# Top.net
KiCad netlist of a schematic drawn in Altium Designer
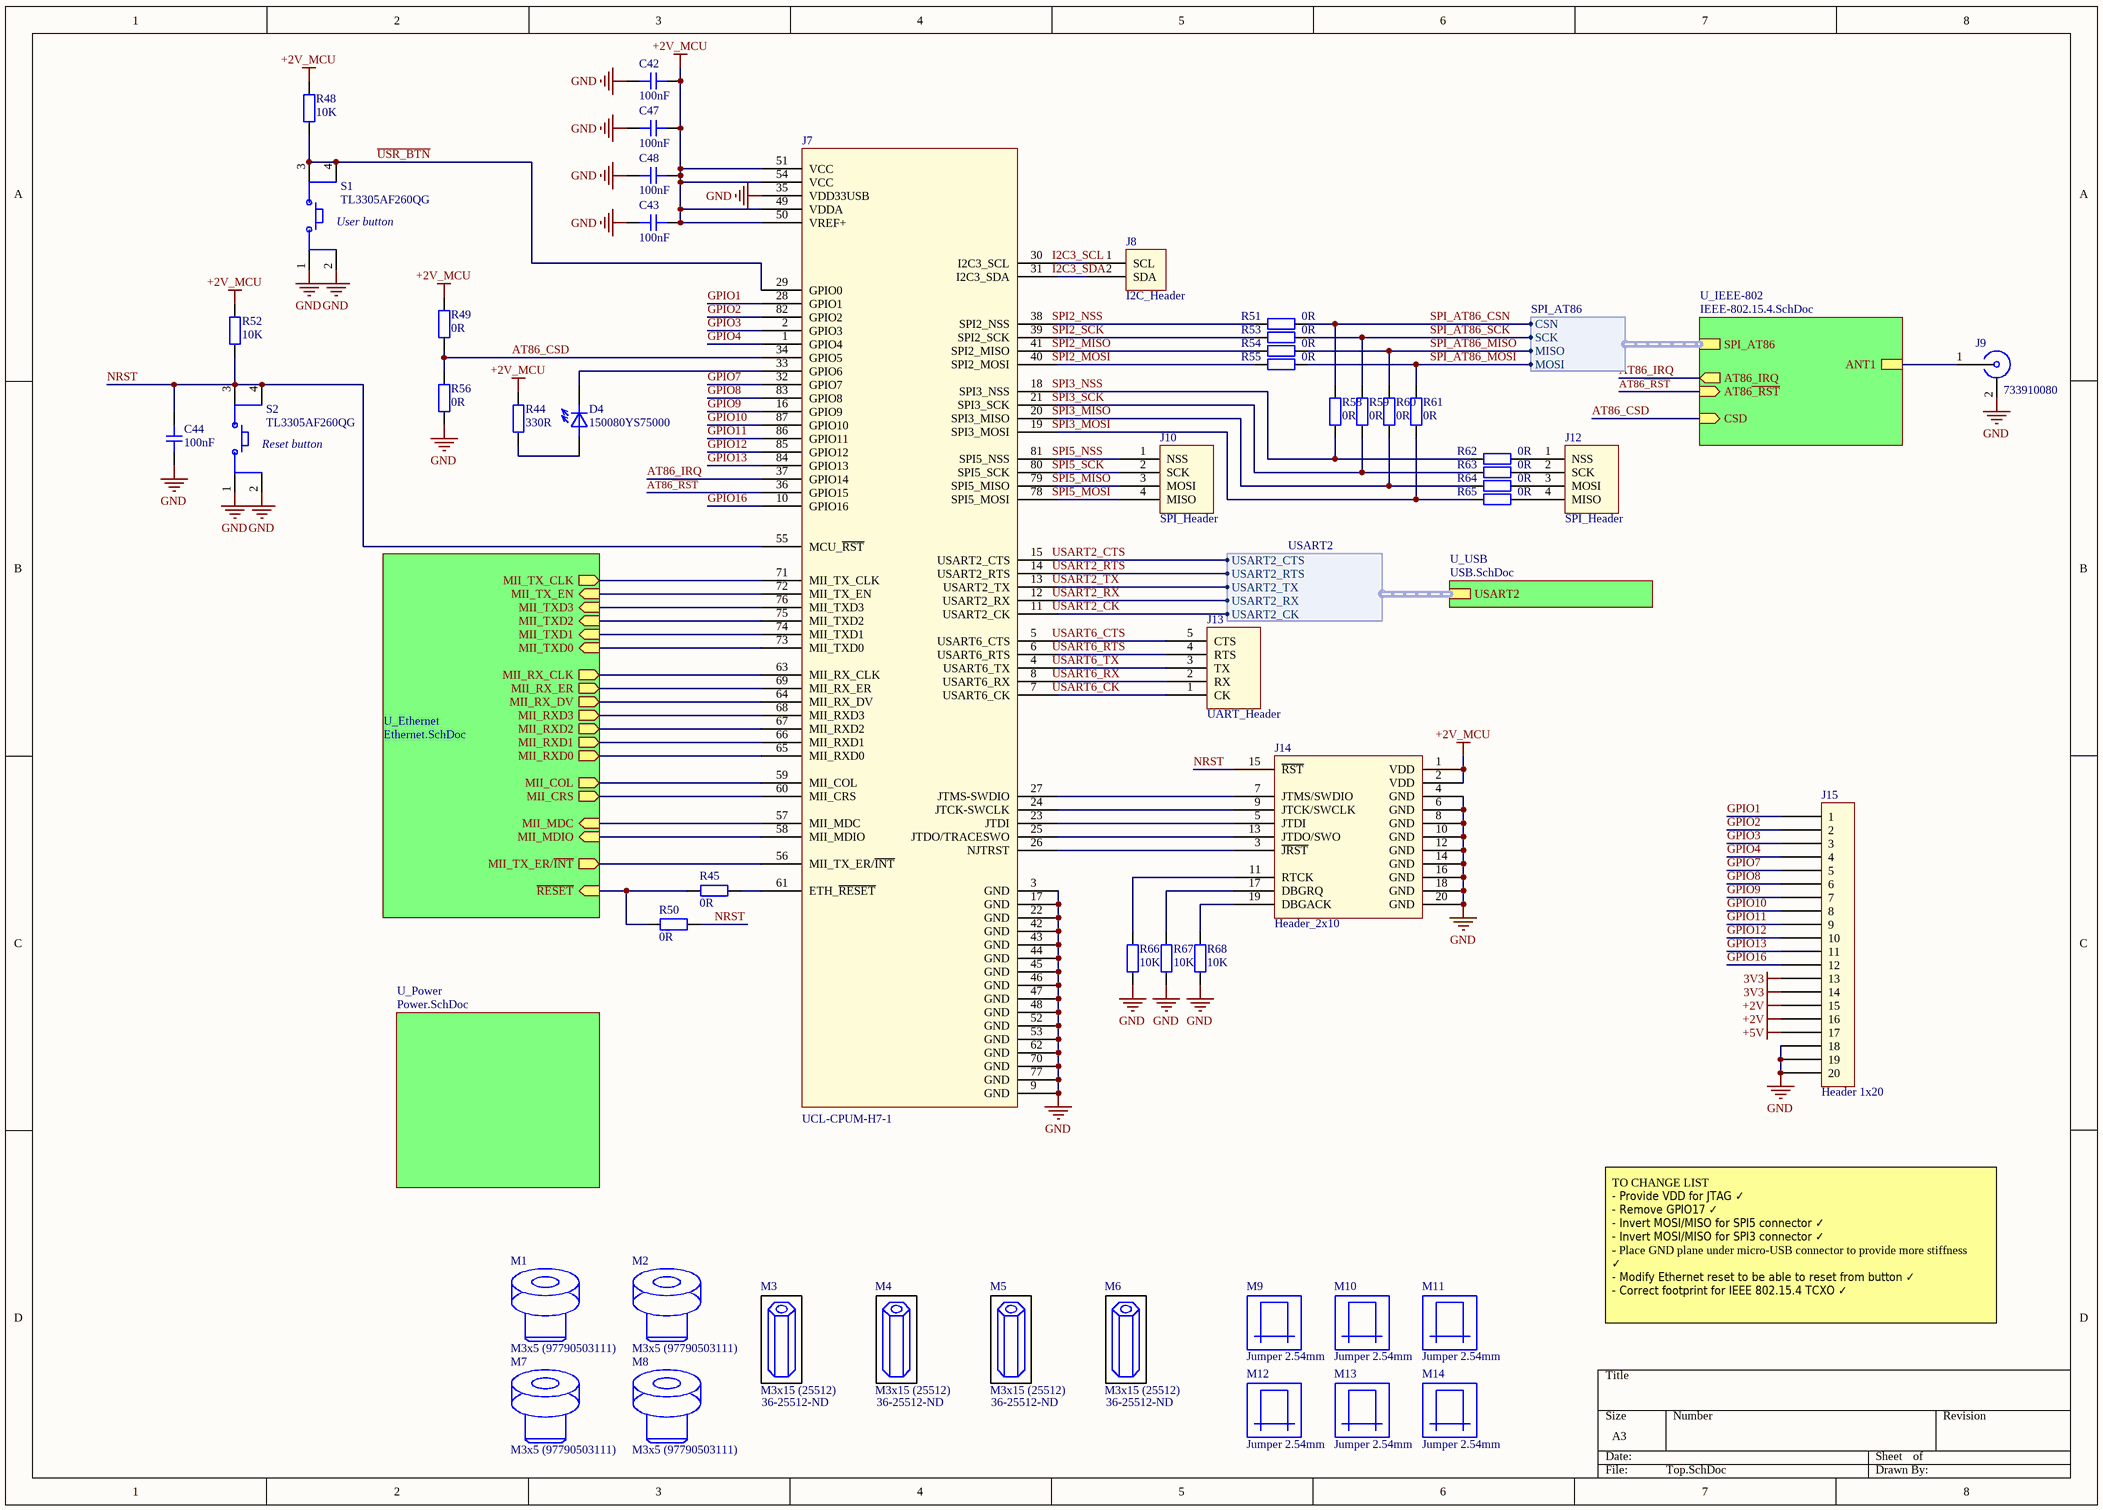
[diagram p0: Top.SchDoc]

(export (version "E")
  (design (tool "Eeschema 10.0.6"))
  (components
    (comp (ref "C42")
      (value "100nF")
      (footprint "Capacitor-0603")
      (fields (field (name "Comment") "C-100nF-0603"))
      (libsource (lib "Components") (part "C-100nF-0603"))
    )
    (comp (ref "C43")
      (value "100nF")
      (footprint "Capacitor-0603")
      (fields (field (name "Comment") "C-100nF-0603"))
      (libsource (lib "Components") (part "C-100nF-0603"))
    )
    (comp (ref "C44")
      (value "100nF")
      (footprint "Capacitor-0603")
      (fields (field (name "Comment") "C-100nF-0603"))
      (libsource (lib "Components") (part "C-100nF-0603"))
    )
    (comp (ref "C47")
      (value "100nF")
      (footprint "Capacitor-0603")
      (fields (field (name "Comment") "C-100nF-0603"))
      (libsource (lib "Components") (part "C-100nF-0603"))
    )
    (comp (ref "C48")
      (value "100nF")
      (footprint "Capacitor-0603")
      (fields (field (name "Comment") "C-100nF-0603"))
      (libsource (lib "Components") (part "C-100nF-0603"))
    )
    (comp (ref "D4")
      (value "150080YS75000")
      (footprint "150080YS75000")
      (libsource (lib "Components") (part "150080YS75000"))
    )
    (comp (ref "J7")
      (value "UCL-CPUM-H7-1")
      (footprint "UCL-CPUM-H7-1")
      (libsource (lib "Components") (part "UCL-CPUM-H7-1"))
    )
    (comp (ref "J8")
      (value "I2C_Header")
      (footprint "I2C_header")
      (libsource (lib "Components") (part "I2C_Header"))
    )
    (comp (ref "J9")
      (value "733910080")
      (footprint "SMA_733910080")
      (libsource (lib "Components") (part "SMA_733910080"))
    )
    (comp (ref "J10")
      (value "SPI_Header")
      (footprint "SPI_Header")
      (libsource (lib "Components") (part "SPI_Header"))
    )
    (comp (ref "J12")
      (value "SPI_Header")
      (footprint "SPI_Header")
      (libsource (lib "Components") (part "SPI_Header"))
    )
    (comp (ref "J13")
      (value "UART_Header")
      (footprint "UART_Header")
      (libsource (lib "Components") (part "UART_Header"))
    )
    (comp (ref "J14")
      (value "Header_2x10")
      (footprint "JTAG_Header")
      (libsource (lib "Components") (part "JTAG_Header"))
    )
    (comp (ref "J15")
      (value "Header 1x20")
      (footprint "GPIO_Header")
      (libsource (lib "Components") (part "GPIO_Header"))
    )
    (comp (ref "M1")
      (value "M3x5 (97790503111)")
      (footprint "Screw_M3")
      (libsource (lib "Components") (part "Screw_M3x5"))
    )
    (comp (ref "M2")
      (value "M3x5 (97790503111)")
      (footprint "Screw_M3")
      (libsource (lib "Components") (part "Screw_M3x5"))
    )
    (comp (ref "M3")
      (value "M3x15 (25512)")
      (fields (field (name "SUPPLIER PART NUMBER 1") "36-25512-ND"))
      (libsource (lib "Components") (part "Standoff_hex_M3_15mm_25512"))
    )
    (comp (ref "M4")
      (value "M3x15 (25512)")
      (fields (field (name "SUPPLIER PART NUMBER 1") "36-25512-ND"))
      (libsource (lib "Components") (part "Standoff_hex_M3_15mm_25512"))
    )
    (comp (ref "M5")
      (value "M3x15 (25512)")
      (fields (field (name "SUPPLIER PART NUMBER 1") "36-25512-ND"))
      (libsource (lib "Components") (part "Standoff_hex_M3_15mm_25512"))
    )
    (comp (ref "M6")
      (value "M3x15 (25512)")
      (fields (field (name "SUPPLIER PART NUMBER 1") "36-25512-ND"))
      (libsource (lib "Components") (part "Standoff_hex_M3_15mm_25512"))
    )
    (comp (ref "M7")
      (value "M3x5 (97790503111)")
      (footprint "Screw_M3")
      (libsource (lib "Components") (part "Screw_M3x5"))
    )
    (comp (ref "M8")
      (value "M3x5 (97790503111)")
      (footprint "Screw_M3")
      (libsource (lib "Components") (part "Screw_M3x5"))
    )
    (comp (ref "M9") (value "Jumper 2.54mm") (libsource (lib "Components") (part "QPC02SXGN-RC")))
    (comp (ref "M10") (value "Jumper 2.54mm") (libsource (lib "Components") (part "QPC02SXGN-RC")))
    (comp (ref "M11") (value "Jumper 2.54mm") (libsource (lib "Components") (part "QPC02SXGN-RC")))
    (comp (ref "M12") (value "Jumper 2.54mm") (libsource (lib "Components") (part "QPC02SXGN-RC")))
    (comp (ref "M13") (value "Jumper 2.54mm") (libsource (lib "Components") (part "QPC02SXGN-RC")))
    (comp (ref "M14") (value "Jumper 2.54mm") (libsource (lib "Components") (part "QPC02SXGN-RC")))
    (comp (ref "R44")
      (value "330R")
      (footprint "Resistor-0603")
      (fields (field (name "Comment") "R-330R-0603"))
      (libsource (lib "Components") (part "R-330R-0603"))
    )
    (comp (ref "R45")
      (value "0R")
      (footprint "Resistor-0603")
      (fields (field (name "Comment") "R-0R-0603"))
      (libsource (lib "Components") (part "R-0R-0603"))
    )
    (comp (ref "R48")
      (value "10K")
      (footprint "Resistor-0603")
      (fields (field (name "Comment") "R-10K-0603"))
      (libsource (lib "Components") (part "R-10K-0603"))
    )
    (comp (ref "R49")
      (value "0R")
      (footprint "Resistor-0603")
      (fields (field (name "Comment") "R-0R-0603"))
      (libsource (lib "Components") (part "R-0R-0603"))
    )
    (comp (ref "R50")
      (value "0R")
      (footprint "Resistor-0603")
      (fields (field (name "Comment") "R-0R-0603"))
      (libsource (lib "Components") (part "R-0R-0603"))
    )
    (comp (ref "R51")
      (value "0R")
      (footprint "Resistor-0603")
      (fields (field (name "Comment") "R-0R-0603"))
      (libsource (lib "Components") (part "R-0R-0603"))
    )
    (comp (ref "R52")
      (value "10K")
      (footprint "Resistor-0603")
      (fields (field (name "Comment") "R-10K-0603"))
      (libsource (lib "Components") (part "R-10K-0603"))
    )
    (comp (ref "R53")
      (value "0R")
      (footprint "Resistor-0603")
      (fields (field (name "Comment") "R-0R-0603"))
      (libsource (lib "Components") (part "R-0R-0603"))
    )
    (comp (ref "R54")
      (value "0R")
      (footprint "Resistor-0603")
      (fields (field (name "Comment") "R-0R-0603"))
      (libsource (lib "Components") (part "R-0R-0603"))
    )
    (comp (ref "R55")
      (value "0R")
      (footprint "Resistor-0603")
      (fields (field (name "Comment") "R-0R-0603"))
      (libsource (lib "Components") (part "R-0R-0603"))
    )
    (comp (ref "R56")
      (value "0R")
      (footprint "Resistor-0603")
      (fields (field (name "Comment") "R-0R-0603"))
      (libsource (lib "Components") (part "R-0R-0603"))
    )
    (comp (ref "R58")
      (value "0R")
      (footprint "Resistor-0603")
      (fields (field (name "Comment") "R-0R-0603"))
      (libsource (lib "Components") (part "R-0R-0603"))
    )
    (comp (ref "R59")
      (value "0R")
      (footprint "Resistor-0603")
      (fields (field (name "Comment") "R-0R-0603"))
      (libsource (lib "Components") (part "R-0R-0603"))
    )
    (comp (ref "R60")
      (value "0R")
      (footprint "Resistor-0603")
      (fields (field (name "Comment") "R-0R-0603"))
      (libsource (lib "Components") (part "R-0R-0603"))
    )
    (comp (ref "R61")
      (value "0R")
      (footprint "Resistor-0603")
      (fields (field (name "Comment") "R-0R-0603"))
      (libsource (lib "Components") (part "R-0R-0603"))
    )
    (comp (ref "R62")
      (value "0R")
      (footprint "Resistor-0603")
      (fields (field (name "Comment") "R-0R-0603"))
      (libsource (lib "Components") (part "R-0R-0603"))
    )
    (comp (ref "R63")
      (value "0R")
      (footprint "Resistor-0603")
      (fields (field (name "Comment") "R-0R-0603"))
      (libsource (lib "Components") (part "R-0R-0603"))
    )
    (comp (ref "R64")
      (value "0R")
      (footprint "Resistor-0603")
      (fields (field (name "Comment") "R-0R-0603"))
      (libsource (lib "Components") (part "R-0R-0603"))
    )
    (comp (ref "R65")
      (value "0R")
      (footprint "Resistor-0603")
      (fields (field (name "Comment") "R-0R-0603"))
      (libsource (lib "Components") (part "R-0R-0603"))
    )
    (comp (ref "R66")
      (value "10K")
      (footprint "Resistor-0603")
      (fields (field (name "Comment") "R-10K-0603"))
      (libsource (lib "Components") (part "R-10K-0603"))
    )
    (comp (ref "R67")
      (value "10K")
      (footprint "Resistor-0603")
      (fields (field (name "Comment") "R-10K-0603"))
      (libsource (lib "Components") (part "R-10K-0603"))
    )
    (comp (ref "R68")
      (value "10K")
      (footprint "Resistor-0603")
      (fields (field (name "Comment") "R-10K-0603"))
      (libsource (lib "Components") (part "R-10K-0603"))
    )
    (comp (ref "S1")
      (value "TL3305AF260QG")
      (footprint "TL3305AF260QG")
      (libsource (lib "Components") (part "TL3305AF260QG"))
    )
    (comp (ref "S2")
      (value "TL3305AF260QG")
      (footprint "TL3305AF260QG")
      (libsource (lib "Components") (part "TL3305AF260QG"))
    )
  )
  (nets
    (net (code "3") (name "+2V") (class "Default")
      (node (ref "J15") (pin "15") (pinfunction "15_15") (pintype "passive"))
      (node (ref "J15") (pin "16") (pinfunction "16_16") (pintype "passive"))
    )
    (net (code "4") (name "+2V_MCU") (class "Default")
      (node (ref "C42") (pin "2") (pinfunction "2_2") (pintype "passive"))
      (node (ref "C43") (pin "2") (pinfunction "2_2") (pintype "passive"))
      (node (ref "C47") (pin "2") (pinfunction "2_2") (pintype "passive"))
      (node (ref "C48") (pin "2") (pinfunction "2_2") (pintype "passive"))
      (node (ref "J14") (pin "1") (pinfunction "VDD_1") (pintype "passive"))
      (node (ref "J14") (pin "2") (pinfunction "VDD_2") (pintype "passive"))
      (node (ref "J7") (pin "49") (pinfunction "VDDA_49") (pintype "passive"))
      (node (ref "J7") (pin "50") (pinfunction "VREF+_50") (pintype "passive"))
      (node (ref "J7") (pin "51") (pinfunction "VCC_51") (pintype "passive"))
      (node (ref "J7") (pin "54") (pinfunction "VCC_54") (pintype "passive"))
      (node (ref "R44") (pin "2") (pinfunction "2_2") (pintype "passive"))
      (node (ref "R48") (pin "2") (pinfunction "2_2") (pintype "passive"))
      (node (ref "R49") (pin "2") (pinfunction "2_2") (pintype "passive"))
      (node (ref "R52") (pin "2") (pinfunction "2_2") (pintype "passive"))
    )
    (net (code "5") (name "+5V") (class "Default")
      (node (ref "J15") (pin "17") (pinfunction "17_17") (pintype "passive"))
    )
    (net (code "6") (name "/ANT1") (class "Default")
      (node (ref "J9") (pin "1") (pinfunction "SIG_1") (pintype "passive"))
    )
    (net (code "7") (name "/AT86_CSD") (class "Default")
      (node (ref "J7") (pin "34") (pinfunction "GPIO5_34") (pintype "passive"))
      (node (ref "R49") (pin "1") (pinfunction "1_1") (pintype "passive"))
      (node (ref "R56") (pin "2") (pinfunction "2_2") (pintype "passive"))
    )
    (net (code "8") (name "/AT86_IRQ") (class "Default")
      (node (ref "J7") (pin "37") (pinfunction "GPIO14_37") (pintype "passive"))
    )
    (net (code "9") (name "/AT86~{_RST}") (class "Default")
      (node (ref "J7") (pin "36") (pinfunction "GPIO15_36") (pintype "passive"))
    )
    (net (code "10") (name "/GPIO1") (class "Default")
      (node (ref "J15") (pin "1") (pinfunction "1_1") (pintype "passive"))
      (node (ref "J7") (pin "28") (pinfunction "GPIO1_28") (pintype "passive"))
    )
    (net (code "11") (name "/GPIO2") (class "Default")
      (node (ref "J15") (pin "2") (pinfunction "2_2") (pintype "passive"))
      (node (ref "J7") (pin "82") (pinfunction "GPIO2_82") (pintype "passive"))
    )
    (net (code "12") (name "/GPIO3") (class "Default")
      (node (ref "J15") (pin "3") (pinfunction "3_3") (pintype "passive"))
      (node (ref "J7") (pin "2") (pinfunction "GPIO3_2") (pintype "passive"))
    )
    (net (code "13") (name "/GPIO4") (class "Default")
      (node (ref "J15") (pin "4") (pinfunction "4_4") (pintype "passive"))
      (node (ref "J7") (pin "1") (pinfunction "GPIO4_1") (pintype "passive"))
    )
    (net (code "14") (name "/GPIO7") (class "Default")
      (node (ref "J15") (pin "5") (pinfunction "5_5") (pintype "passive"))
      (node (ref "J7") (pin "32") (pinfunction "GPIO7_32") (pintype "passive"))
    )
    (net (code "15") (name "/GPIO8") (class "Default")
      (node (ref "J15") (pin "6") (pinfunction "6_6") (pintype "passive"))
      (node (ref "J7") (pin "83") (pinfunction "GPIO8_83") (pintype "passive"))
    )
    (net (code "16") (name "/GPIO9") (class "Default")
      (node (ref "J15") (pin "7") (pinfunction "7_7") (pintype "passive"))
      (node (ref "J7") (pin "16") (pinfunction "GPIO9_16") (pintype "passive"))
    )
    (net (code "17") (name "/GPIO10") (class "Default")
      (node (ref "J15") (pin "8") (pinfunction "8_8") (pintype "passive"))
      (node (ref "J7") (pin "87") (pinfunction "GPIO10_87") (pintype "passive"))
    )
    (net (code "18") (name "/GPIO11") (class "Default")
      (node (ref "J15") (pin "9") (pinfunction "9_9") (pintype "passive"))
      (node (ref "J7") (pin "86") (pinfunction "GPIO11_86") (pintype "passive"))
    )
    (net (code "19") (name "/GPIO12") (class "Default")
      (node (ref "J15") (pin "10") (pinfunction "10_10") (pintype "passive"))
      (node (ref "J7") (pin "85") (pinfunction "GPIO12_85") (pintype "passive"))
    )
    (net (code "20") (name "/GPIO13") (class "Default")
      (node (ref "J15") (pin "11") (pinfunction "11_11") (pintype "passive"))
      (node (ref "J7") (pin "84") (pinfunction "GPIO13_84") (pintype "passive"))
    )
    (net (code "21") (name "/GPIO16") (class "Default")
      (node (ref "J15") (pin "12") (pinfunction "12_12") (pintype "passive"))
      (node (ref "J7") (pin "10") (pinfunction "GPIO16_10") (pintype "passive"))
    )
    (net (code "24") (name "/MII_COL") (class "Default")
      (node (ref "J7") (pin "59") (pinfunction "MII_COL_59") (pintype "passive"))
    )
    (net (code "25") (name "/MII_CRS") (class "Default")
      (node (ref "J7") (pin "60") (pinfunction "MII_CRS_60") (pintype "passive"))
    )
    (net (code "26") (name "/MII_MDC") (class "Default")
      (node (ref "J7") (pin "57") (pinfunction "MII_MDC_57") (pintype "passive"))
    )
    (net (code "27") (name "/MII_MDIO") (class "Default")
      (node (ref "J7") (pin "58") (pinfunction "MII_MDIO_58") (pintype "passive"))
    )
    (net (code "28") (name "/MII_RXD0") (class "Default")
      (node (ref "J7") (pin "65") (pinfunction "MII_RXD0_65") (pintype "passive"))
    )
    (net (code "29") (name "/MII_RXD1") (class "Default")
      (node (ref "J7") (pin "66") (pinfunction "MII_RXD1_66") (pintype "passive"))
    )
    (net (code "30") (name "/MII_RXD2") (class "Default")
      (node (ref "J7") (pin "67") (pinfunction "MII_RXD2_67") (pintype "passive"))
    )
    (net (code "31") (name "/MII_RXD3") (class "Default")
      (node (ref "J7") (pin "68") (pinfunction "MII_RXD3_68") (pintype "passive"))
    )
    (net (code "32") (name "/MII_RX_CLK") (class "Default")
      (node (ref "J7") (pin "63") (pinfunction "MII_RX_CLK_63") (pintype "passive"))
    )
    (net (code "33") (name "/MII_RX_DV") (class "Default")
      (node (ref "J7") (pin "64") (pinfunction "MII_RX_DV_64") (pintype "passive"))
    )
    (net (code "34") (name "/MII_RX_ER") (class "Default")
      (node (ref "J7") (pin "69") (pinfunction "MII_RX_ER_69") (pintype "passive"))
    )
    (net (code "35") (name "/MII_TXD0") (class "Default")
      (node (ref "J7") (pin "73") (pinfunction "MII_TXD0_73") (pintype "passive"))
    )
    (net (code "36") (name "/MII_TXD1") (class "Default")
      (node (ref "J7") (pin "74") (pinfunction "MII_TXD1_74") (pintype "passive"))
    )
    (net (code "37") (name "/MII_TXD2") (class "Default")
      (node (ref "J7") (pin "75") (pinfunction "MII_TXD2_75") (pintype "passive"))
    )
    (net (code "38") (name "/MII_TXD3") (class "Default")
      (node (ref "J7") (pin "76") (pinfunction "MII_TXD3_76") (pintype "passive"))
    )
    (net (code "39") (name "/MII_TX_CLK") (class "Default")
      (node (ref "J7") (pin "71") (pinfunction "MII_TX_CLK_71") (pintype "passive"))
    )
    (net (code "40") (name "/MII_TX_EN") (class "Default")
      (node (ref "J7") (pin "72") (pinfunction "MII_TX_EN_72") (pintype "passive"))
    )
    (net (code "41") (name "/MII_TX_ER{slash}~{INT}") (class "Default")
      (node (ref "J7") (pin "56") (pinfunction "MII_TX_ER/~{INT}_56") (pintype "passive"))
    )
    (net (code "42") (name "/NRST") (class "Default")
      (node (ref "C44") (pin "2") (pinfunction "2_2") (pintype "passive"))
      (node (ref "J14") (pin "15") (pinfunction "~{RST}_15") (pintype "passive"))
      (node (ref "J7") (pin "55") (pinfunction "MCU_~{RST}_55") (pintype "passive"))
      (node (ref "R50") (pin "2") (pinfunction "2_2") (pintype "passive"))
      (node (ref "R52") (pin "1") (pinfunction "1_1") (pintype "passive"))
      (node (ref "S2") (pin "3") (pinfunction "3_3") (pintype "passive"))
      (node (ref "S2") (pin "4") (pinfunction "4_4") (pintype "passive"))
    )
    (net (code "55") (name "/SPI_AT86_CSN") (class "Default")
      (node (ref "R51") (pin "2") (pinfunction "2_2") (pintype "passive"))
      (node (ref "R58") (pin "2") (pinfunction "2_2") (pintype "passive"))
    )
    (net (code "56") (name "/SPI_AT86_MISO") (class "Default")
      (node (ref "R54") (pin "2") (pinfunction "2_2") (pintype "passive"))
      (node (ref "R60") (pin "2") (pinfunction "2_2") (pintype "passive"))
    )
    (net (code "57") (name "/SPI_AT86_MOSI") (class "Default")
      (node (ref "R55") (pin "2") (pinfunction "2_2") (pintype "passive"))
      (node (ref "R61") (pin "2") (pinfunction "2_2") (pintype "passive"))
    )
    (net (code "58") (name "/SPI_AT86_SCK") (class "Default")
      (node (ref "R53") (pin "2") (pinfunction "2_2") (pintype "passive"))
      (node (ref "R59") (pin "2") (pinfunction "2_2") (pintype "passive"))
    )
    (net (code "71") (name "/~{RESET}") (class "Default")
      (node (ref "R45") (pin "1") (pinfunction "1_1") (pintype "passive"))
      (node (ref "R50") (pin "1") (pinfunction "1_1") (pintype "passive"))
    )
    (net (code "72") (name "/~{USR_BTN}") (class "Default")
      (node (ref "J7") (pin "29") (pinfunction "GPIO0_29") (pintype "passive"))
      (node (ref "R48") (pin "1") (pinfunction "1_1") (pintype "passive"))
      (node (ref "S1") (pin "3") (pinfunction "3_3") (pintype "passive"))
      (node (ref "S1") (pin "4") (pinfunction "4_4") (pintype "passive"))
    )
    (net (code "73") (name "3V3") (class "Default")
      (node (ref "J15") (pin "13") (pinfunction "13_13") (pintype "passive"))
      (node (ref "J15") (pin "14") (pinfunction "14_14") (pintype "passive"))
    )
    (net (code "74") (name "GND") (class "Default")
      (node (ref "C42") (pin "1") (pinfunction "1_1") (pintype "passive"))
      (node (ref "C43") (pin "1") (pinfunction "1_1") (pintype "passive"))
      (node (ref "C44") (pin "1") (pinfunction "1_1") (pintype "passive"))
      (node (ref "C47") (pin "1") (pinfunction "1_1") (pintype "passive"))
      (node (ref "C48") (pin "1") (pinfunction "1_1") (pintype "passive"))
      (node (ref "J14") (pin "10") (pinfunction "GND_10") (pintype "passive"))
      (node (ref "J14") (pin "12") (pinfunction "GND_12") (pintype "passive"))
      (node (ref "J14") (pin "14") (pinfunction "GND_14") (pintype "passive"))
      (node (ref "J14") (pin "16") (pinfunction "GND_16") (pintype "passive"))
      (node (ref "J14") (pin "18") (pinfunction "GND_18") (pintype "passive"))
      (node (ref "J14") (pin "20") (pinfunction "GND_20") (pintype "passive"))
      (node (ref "J14") (pin "4") (pinfunction "GND_4") (pintype "passive"))
      (node (ref "J14") (pin "6") (pinfunction "GND_6") (pintype "passive"))
      (node (ref "J14") (pin "8") (pinfunction "GND_8") (pintype "passive"))
      (node (ref "J15") (pin "18") (pinfunction "18_18") (pintype "passive"))
      (node (ref "J15") (pin "19") (pinfunction "19_19") (pintype "passive"))
      (node (ref "J15") (pin "20") (pinfunction "20_20") (pintype "passive"))
      (node (ref "J7") (pin "17") (pinfunction "GND_17") (pintype "passive"))
      (node (ref "J7") (pin "22") (pinfunction "GND_22") (pintype "passive"))
      (node (ref "J7") (pin "3") (pinfunction "GND_3") (pintype "passive"))
      (node (ref "J7") (pin "35") (pinfunction "VDD33USB_35") (pintype "passive"))
      (node (ref "J7") (pin "42") (pinfunction "GND_42") (pintype "passive"))
      (node (ref "J7") (pin "43") (pinfunction "GND_43") (pintype "passive"))
      (node (ref "J7") (pin "44") (pinfunction "GND_44") (pintype "passive"))
      (node (ref "J7") (pin "45") (pinfunction "GND_45") (pintype "passive"))
      (node (ref "J7") (pin "46") (pinfunction "GND_46") (pintype "passive"))
      (node (ref "J7") (pin "47") (pinfunction "GND_47") (pintype "passive"))
      (node (ref "J7") (pin "48") (pinfunction "GND_48") (pintype "passive"))
      (node (ref "J7") (pin "52") (pinfunction "GND_52") (pintype "passive"))
      (node (ref "J7") (pin "53") (pinfunction "GND_53") (pintype "passive"))
      (node (ref "J7") (pin "62") (pinfunction "GND_62") (pintype "passive"))
      (node (ref "J7") (pin "70") (pinfunction "GND_70") (pintype "passive"))
      (node (ref "J7") (pin "77") (pinfunction "GND_77") (pintype "passive"))
      (node (ref "J7") (pin "9") (pinfunction "GND_9") (pintype "passive"))
      (node (ref "J9") (pin "2") (pinfunction "GND_2") (pintype "passive"))
      (node (ref "R56") (pin "1") (pinfunction "1_1") (pintype "passive"))
      (node (ref "R66") (pin "1") (pinfunction "1_1") (pintype "passive"))
      (node (ref "R67") (pin "1") (pinfunction "1_1") (pintype "passive"))
      (node (ref "R68") (pin "1") (pinfunction "1_1") (pintype "passive"))
      (node (ref "S1") (pin "1") (pinfunction "1_1") (pintype "passive"))
      (node (ref "S1") (pin "2") (pinfunction "2_2") (pintype "passive"))
      (node (ref "S2") (pin "1") (pinfunction "1_1") (pintype "passive"))
      (node (ref "S2") (pin "2") (pinfunction "2_2") (pintype "passive"))
    )
    (net (code "75") (name "Net-(D4-Pad2)") (class "Default")
      (node (ref "D4") (pin "2") (pinfunction "2_2") (pintype "passive"))
      (node (ref "R44") (pin "1") (pinfunction "1_1") (pintype "passive"))
    )
    (net (code "76") (name "Net-(J7-ETH_~{RESET})") (class "Default")
      (node (ref "J7") (pin "61") (pinfunction "ETH_~{RESET}_61") (pintype "passive"))
      (node (ref "R45") (pin "2") (pinfunction "2_2") (pintype "passive"))
    )
    (net (code "77") (name "Net-(J7-GPIO6)") (class "Default")
      (node (ref "D4") (pin "1") (pinfunction "1_1") (pintype "passive"))
      (node (ref "J7") (pin "33") (pinfunction "GPIO6_33") (pintype "passive"))
    )
    (net (code "78") (name "Net-(J7-I2C3_SCL)") (class "Default")
      (node (ref "J7") (pin "30") (pinfunction "I2C3_SCL_30") (pintype "passive"))
      (node (ref "J8") (pin "1") (pinfunction "SCL_1") (pintype "passive"))
    )
    (net (code "79") (name "Net-(J7-I2C3_SDA)") (class "Default")
      (node (ref "J7") (pin "31") (pinfunction "I2C3_SDA_31") (pintype "passive"))
      (node (ref "J8") (pin "2") (pinfunction "SDA_2") (pintype "passive"))
    )
    (net (code "80") (name "Net-(J7-SPI2_MISO)") (class "Default")
      (node (ref "J7") (pin "41") (pinfunction "SPI2_MISO_41") (pintype "passive"))
      (node (ref "R54") (pin "1") (pinfunction "1_1") (pintype "passive"))
    )
    (net (code "81") (name "Net-(J7-SPI2_MOSI)") (class "Default")
      (node (ref "J7") (pin "40") (pinfunction "SPI2_MOSI_40") (pintype "passive"))
      (node (ref "R55") (pin "1") (pinfunction "1_1") (pintype "passive"))
    )
    (net (code "82") (name "Net-(J7-SPI2_NSS)") (class "Default")
      (node (ref "J7") (pin "38") (pinfunction "SPI2_NSS_38") (pintype "passive"))
      (node (ref "R51") (pin "1") (pinfunction "1_1") (pintype "passive"))
    )
    (net (code "83") (name "Net-(J7-SPI2_SCK)") (class "Default")
      (node (ref "J7") (pin "39") (pinfunction "SPI2_SCK_39") (pintype "passive"))
      (node (ref "R53") (pin "1") (pinfunction "1_1") (pintype "passive"))
    )
    (net (code "84") (name "Net-(J7-SPI3_MISO)") (class "Default")
      (node (ref "J7") (pin "20") (pinfunction "SPI3_MISO_20") (pintype "passive"))
      (node (ref "R60") (pin "1") (pinfunction "1_1") (pintype "passive"))
      (node (ref "R64") (pin "1") (pinfunction "1_1") (pintype "passive"))
    )
    (net (code "85") (name "Net-(J7-SPI3_MOSI)") (class "Default")
      (node (ref "J7") (pin "19") (pinfunction "SPI3_MOSI_19") (pintype "passive"))
      (node (ref "R61") (pin "1") (pinfunction "1_1") (pintype "passive"))
      (node (ref "R65") (pin "1") (pinfunction "1_1") (pintype "passive"))
    )
    (net (code "86") (name "Net-(J7-SPI3_NSS)") (class "Default")
      (node (ref "J7") (pin "18") (pinfunction "SPI3_NSS_18") (pintype "passive"))
      (node (ref "R58") (pin "1") (pinfunction "1_1") (pintype "passive"))
      (node (ref "R62") (pin "1") (pinfunction "1_1") (pintype "passive"))
    )
    (net (code "87") (name "Net-(J7-SPI3_SCK)") (class "Default")
      (node (ref "J7") (pin "21") (pinfunction "SPI3_SCK_21") (pintype "passive"))
      (node (ref "R59") (pin "1") (pinfunction "1_1") (pintype "passive"))
      (node (ref "R63") (pin "1") (pinfunction "1_1") (pintype "passive"))
    )
    (net (code "88") (name "Net-(J10-MISO)") (class "Default")
      (node (ref "J10") (pin "4") (pinfunction "MISO_4") (pintype "passive"))
      (node (ref "J7") (pin "78") (pinfunction "SPI5_MOSI_78") (pintype "passive"))
    )
    (net (code "89") (name "Net-(J10-MOSI)") (class "Default")
      (node (ref "J10") (pin "3") (pinfunction "MOSI_3") (pintype "passive"))
      (node (ref "J7") (pin "79") (pinfunction "SPI5_MISO_79") (pintype "passive"))
    )
    (net (code "90") (name "Net-(J10-NSS)") (class "Default")
      (node (ref "J10") (pin "1") (pinfunction "NSS_1") (pintype "passive"))
      (node (ref "J7") (pin "81") (pinfunction "SPI5_NSS_81") (pintype "passive"))
    )
    (net (code "91") (name "Net-(J10-SCK)") (class "Default")
      (node (ref "J10") (pin "2") (pinfunction "SCK_2") (pintype "passive"))
      (node (ref "J7") (pin "80") (pinfunction "SPI5_SCK_80") (pintype "passive"))
    )
    (net (code "92") (name "Net-(J12-MISO)") (class "Default")
      (node (ref "J12") (pin "4") (pinfunction "MISO_4") (pintype "passive"))
      (node (ref "R65") (pin "2") (pinfunction "2_2") (pintype "passive"))
    )
    (net (code "93") (name "Net-(J12-MOSI)") (class "Default")
      (node (ref "J12") (pin "3") (pinfunction "MOSI_3") (pintype "passive"))
      (node (ref "R64") (pin "2") (pinfunction "2_2") (pintype "passive"))
    )
    (net (code "94") (name "Net-(J12-NSS)") (class "Default")
      (node (ref "J12") (pin "1") (pinfunction "NSS_1") (pintype "passive"))
      (node (ref "R62") (pin "2") (pinfunction "2_2") (pintype "passive"))
    )
    (net (code "95") (name "Net-(J12-SCK)") (class "Default")
      (node (ref "J12") (pin "2") (pinfunction "SCK_2") (pintype "passive"))
      (node (ref "R63") (pin "2") (pinfunction "2_2") (pintype "passive"))
    )
    (net (code "96") (name "Net-(J13-CK)") (class "Default")
      (node (ref "J13") (pin "1") (pinfunction "CK_1") (pintype "passive"))
      (node (ref "J7") (pin "7") (pinfunction "USART6_CK_7") (pintype "passive"))
    )
    (net (code "97") (name "Net-(J13-CTS)") (class "Default")
      (node (ref "J13") (pin "5") (pinfunction "CTS_5") (pintype "passive"))
      (node (ref "J7") (pin "5") (pinfunction "USART6_CTS_5") (pintype "passive"))
    )
    (net (code "98") (name "Net-(J13-RTS)") (class "Default")
      (node (ref "J13") (pin "4") (pinfunction "RTS_4") (pintype "passive"))
      (node (ref "J7") (pin "6") (pinfunction "USART6_RTS_6") (pintype "passive"))
    )
    (net (code "99") (name "Net-(J13-RX)") (class "Default")
      (node (ref "J13") (pin "2") (pinfunction "RX_2") (pintype "passive"))
      (node (ref "J7") (pin "8") (pinfunction "USART6_RX_8") (pintype "passive"))
    )
    (net (code "100") (name "Net-(J13-TX)") (class "Default")
      (node (ref "J13") (pin "3") (pinfunction "TX_3") (pintype "passive"))
      (node (ref "J7") (pin "4") (pinfunction "USART6_TX_4") (pintype "passive"))
    )
    (net (code "101") (name "Net-(J14-DBGACK)") (class "Default")
      (node (ref "J14") (pin "19") (pinfunction "DBGACK_19") (pintype "passive"))
      (node (ref "R68") (pin "2") (pinfunction "2_2") (pintype "passive"))
    )
    (net (code "102") (name "Net-(J14-DBGRQ)") (class "Default")
      (node (ref "J14") (pin "17") (pinfunction "DBGRQ_17") (pintype "passive"))
      (node (ref "R67") (pin "2") (pinfunction "2_2") (pintype "passive"))
    )
    (net (code "103") (name "Net-(J14-JTCK{slash}SWCLK)") (class "Default")
      (node (ref "J14") (pin "9") (pinfunction "JTCK/SWCLK_9") (pintype "passive"))
      (node (ref "J7") (pin "24") (pinfunction "JTCK-SWCLK_24") (pintype "passive"))
    )
    (net (code "104") (name "Net-(J14-JTDI)") (class "Default")
      (node (ref "J14") (pin "5") (pinfunction "JTDI_5") (pintype "passive"))
      (node (ref "J7") (pin "23") (pinfunction "JTDI_23") (pintype "passive"))
    )
    (net (code "105") (name "Net-(J14-JTDO{slash}SWO)") (class "Default")
      (node (ref "J14") (pin "13") (pinfunction "JTDO/SWO_13") (pintype "passive"))
      (node (ref "J7") (pin "25") (pinfunction "JTDO/TRACESWO_25") (pintype "passive"))
    )
    (net (code "106") (name "Net-(J14-JTMS{slash}SWDIO)") (class "Default")
      (node (ref "J14") (pin "7") (pinfunction "JTMS/SWDIO_7") (pintype "passive"))
      (node (ref "J7") (pin "27") (pinfunction "JTMS-SWDIO_27") (pintype "passive"))
    )
    (net (code "107") (name "Net-(J14-RTCK)") (class "Default")
      (node (ref "J14") (pin "11") (pinfunction "RTCK_11") (pintype "passive"))
      (node (ref "R66") (pin "2") (pinfunction "2_2") (pintype "passive"))
    )
    (net (code "108") (name "Net-(J14-~{JRST})") (class "Default")
      (node (ref "J14") (pin "3") (pinfunction "~{JRST}_3") (pintype "passive"))
      (node (ref "J7") (pin "26") (pinfunction "NJTRST_26") (pintype "passive"))
    )
    (net (code "109") (name "unconnected-(J7-USART2_CK-Pad11)") (class "Default")
      (node (ref "J7") (pin "11") (pinfunction "USART2_CK_11") (pintype "passive"))
    )
    (net (code "110") (name "unconnected-(J7-USART2_CTS-Pad15)") (class "Default")
      (node (ref "J7") (pin "15") (pinfunction "USART2_CTS_15") (pintype "passive"))
    )
    (net (code "111") (name "unconnected-(J7-USART2_RTS-Pad14)") (class "Default")
      (node (ref "J7") (pin "14") (pinfunction "USART2_RTS_14") (pintype "passive"))
    )
    (net (code "112") (name "unconnected-(J7-USART2_RX-Pad12)") (class "Default")
      (node (ref "J7") (pin "12") (pinfunction "USART2_RX_12") (pintype "passive"))
    )
    (net (code "113") (name "unconnected-(J7-USART2_TX-Pad13)") (class "Default")
      (node (ref "J7") (pin "13") (pinfunction "USART2_TX_13") (pintype "passive"))
    )
  )
)
